# rtc.net
KiCad netlist of a schematic drawn in Altium Designer
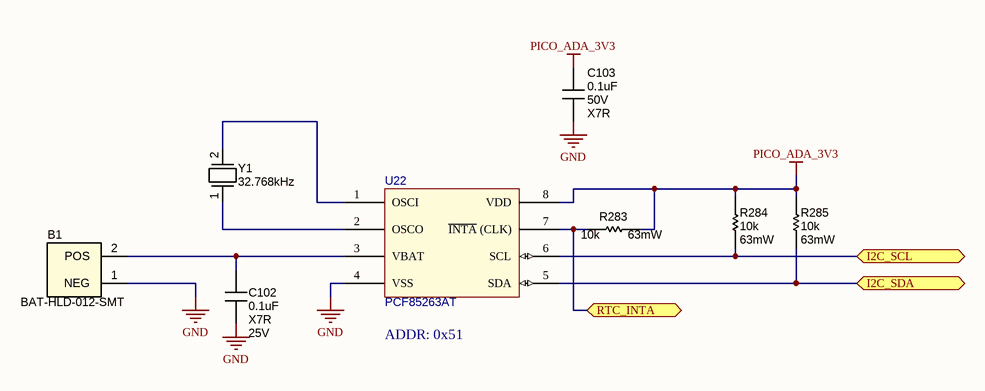
[diagram p0: rtc.SchDoc]

(export (version "E")
  (design (tool "Eeschema 10.0.6"))
  (components
    (comp (ref "B1")
      (value "BAT-HLD-012-SMT")
      (footprint "BAT-HLD-012-SMT")
      (description "BATTERY HOLDER COIN 12MM PC PIN")
      (fields (field (name "MFR") "TE Connectivity Linx"))
      (libsource (lib "General_Library") (part "CMP-002-0005"))
    )
    (comp (ref "C102")
      (value "0.1uF")
      (footprint "CAPC1608X09N")
      (description "CAP CER 0.1UF 25V X7R 0603")
      (fields
        (field (name "TOLERANCE") "10%")
        (field (name "MFR") "Yageo")
        (field (name "TEMP COEFF") "X7R")
        (field (name "VOLTAGE RATING") "25V")
      )
      (libsource (lib "General_Library") (part "CMP-004-0024"))
    )
    (comp (ref "C103")
      (value "0.1uF")
      (footprint "CAPC1005X06N")
      (description "CAP CER SMD 0.1UF 50V X7R 0402")
      (fields
        (field (name "TOLERANCE") "10%")
        (field (name "MFR") "Murata Electronics")
        (field (name "VOLTAGE RATING") "50V")
        (field (name "TEMP COEFF") "X7R")
      )
      (libsource (lib "General_Library") (part "CMP-004-0076"))
    )
    (comp (ref "R283")
      (value "10k")
      (footprint "RESC1005X04N")
      (description "RES SMD 10K OHM 0.5% 1/16W 0402")
      (fields
        (field (name "MFR") "Panasonic Electronic Components")
        (field (name "TOLERANCE") "0.5%")
        (field (name "WATTAGE") "63mW")
      )
      (libsource (lib "General_Library") (part "CMP-025-0026"))
    )
    (comp (ref "R284")
      (value "10k")
      (footprint "RESC1005X04N")
      (description "RES SMD 10K OHM 0.5% 1/16W 0402")
      (fields
        (field (name "MFR") "Panasonic Electronic Components")
        (field (name "TOLERANCE") "0.5%")
        (field (name "WATTAGE") "63mW")
      )
      (libsource (lib "General_Library") (part "CMP-025-0026"))
    )
    (comp (ref "R285")
      (value "10k")
      (footprint "RESC1005X04N")
      (description "RES SMD 10K OHM 0.5% 1/16W 0402")
      (fields
        (field (name "MFR") "Panasonic Electronic Components")
        (field (name "TOLERANCE") "0.5%")
        (field (name "WATTAGE") "63mW")
      )
      (libsource (lib "General_Library") (part "CMP-025-0026"))
    )
    (comp (ref "U22")
      (value "PCF85263AT")
      (footprint "SOIC127P600X175-8N")
      (description "IC OPAMP VFB 1 CIRCUIT 8HVSSOP")
      (fields (field (name "MFR") "NXP"))
      (libsource (lib "General_Library") (part "CMP-017-0120"))
    )
    (comp (ref "Y1")
      (value "32.768kHz")
      (footprint "XTAL_ECS_ECX-12Q")
      (description "Crystal 0.032768MHz ±20ppm (Tol) 12.5pF FUND 90000Ohm Automotive 2-Pin Ultra Mini-CSMD T/R")
      (fields (field (name "MFR") "ECS Inc."))
      (libsource (lib "General_Library") (part "CMP-008-0001"))
    )
  )
  (nets
    (net (code "1") (name "/I2C_SCL") (class "Default")
      (node (ref "R284") (pin "1") (pinfunction "1_1") (pintype "passive"))
      (node (ref "U22") (pin "6") (pinfunction "SCL_6") (pintype "bidirectional"))
    )
    (net (code "2") (name "/I2C_SDA") (class "Default")
      (node (ref "R285") (pin "1") (pinfunction "1_1") (pintype "passive"))
      (node (ref "U22") (pin "5") (pinfunction "SDA_5") (pintype "bidirectional"))
    )
    (net (code "3") (name "/RTC_INTA") (class "Default")
      (node (ref "R283") (pin "2") (pinfunction "2_2") (pintype "passive"))
      (node (ref "U22") (pin "7") (pinfunction "~{INTA}_(CLK)_7") (pintype "passive"))
    )
    (net (code "4") (name "GND") (class "Default")
      (node (ref "B1") (pin "1") (pinfunction "NEG_1") (pintype "passive"))
      (node (ref "C102") (pin "2") (pinfunction "2_2") (pintype "passive"))
      (node (ref "C103") (pin "2") (pinfunction "2_2") (pintype "passive"))
      (node (ref "U22") (pin "4") (pinfunction "VSS_4") (pintype "power_in"))
    )
    (net (code "5") (name "Net-(B1-POS)") (class "Default")
      (node (ref "B1") (pin "2") (pinfunction "POS_2") (pintype "passive"))
      (node (ref "C102") (pin "1") (pinfunction "1_1") (pintype "passive"))
      (node (ref "U22") (pin "3") (pinfunction "VBAT_3") (pintype "passive"))
    )
    (net (code "6") (name "Net-(U22-OSCI)") (class "Default")
      (node (ref "U22") (pin "1") (pinfunction "OSCI_1") (pintype "passive"))
      (node (ref "Y1") (pin "2") (pinfunction "2_2") (pintype "passive"))
    )
    (net (code "7") (name "Net-(U22-OSCO)") (class "Default")
      (node (ref "U22") (pin "2") (pinfunction "OSCO_2") (pintype "passive"))
      (node (ref "Y1") (pin "1") (pinfunction "1_1") (pintype "passive"))
    )
    (net (code "8") (name "PICO_ADA_3V3") (class "Default")
      (node (ref "C103") (pin "1") (pinfunction "1_1") (pintype "passive"))
      (node (ref "R283") (pin "1") (pinfunction "1_1") (pintype "passive"))
      (node (ref "R284") (pin "2") (pinfunction "2_2") (pintype "passive"))
      (node (ref "R285") (pin "2") (pinfunction "2_2") (pintype "passive"))
      (node (ref "U22") (pin "8") (pinfunction "VDD_8") (pintype "passive"))
    )
  )
)
